# controllers.net
KiCad netlist of a schematic drawn in Altium Designer
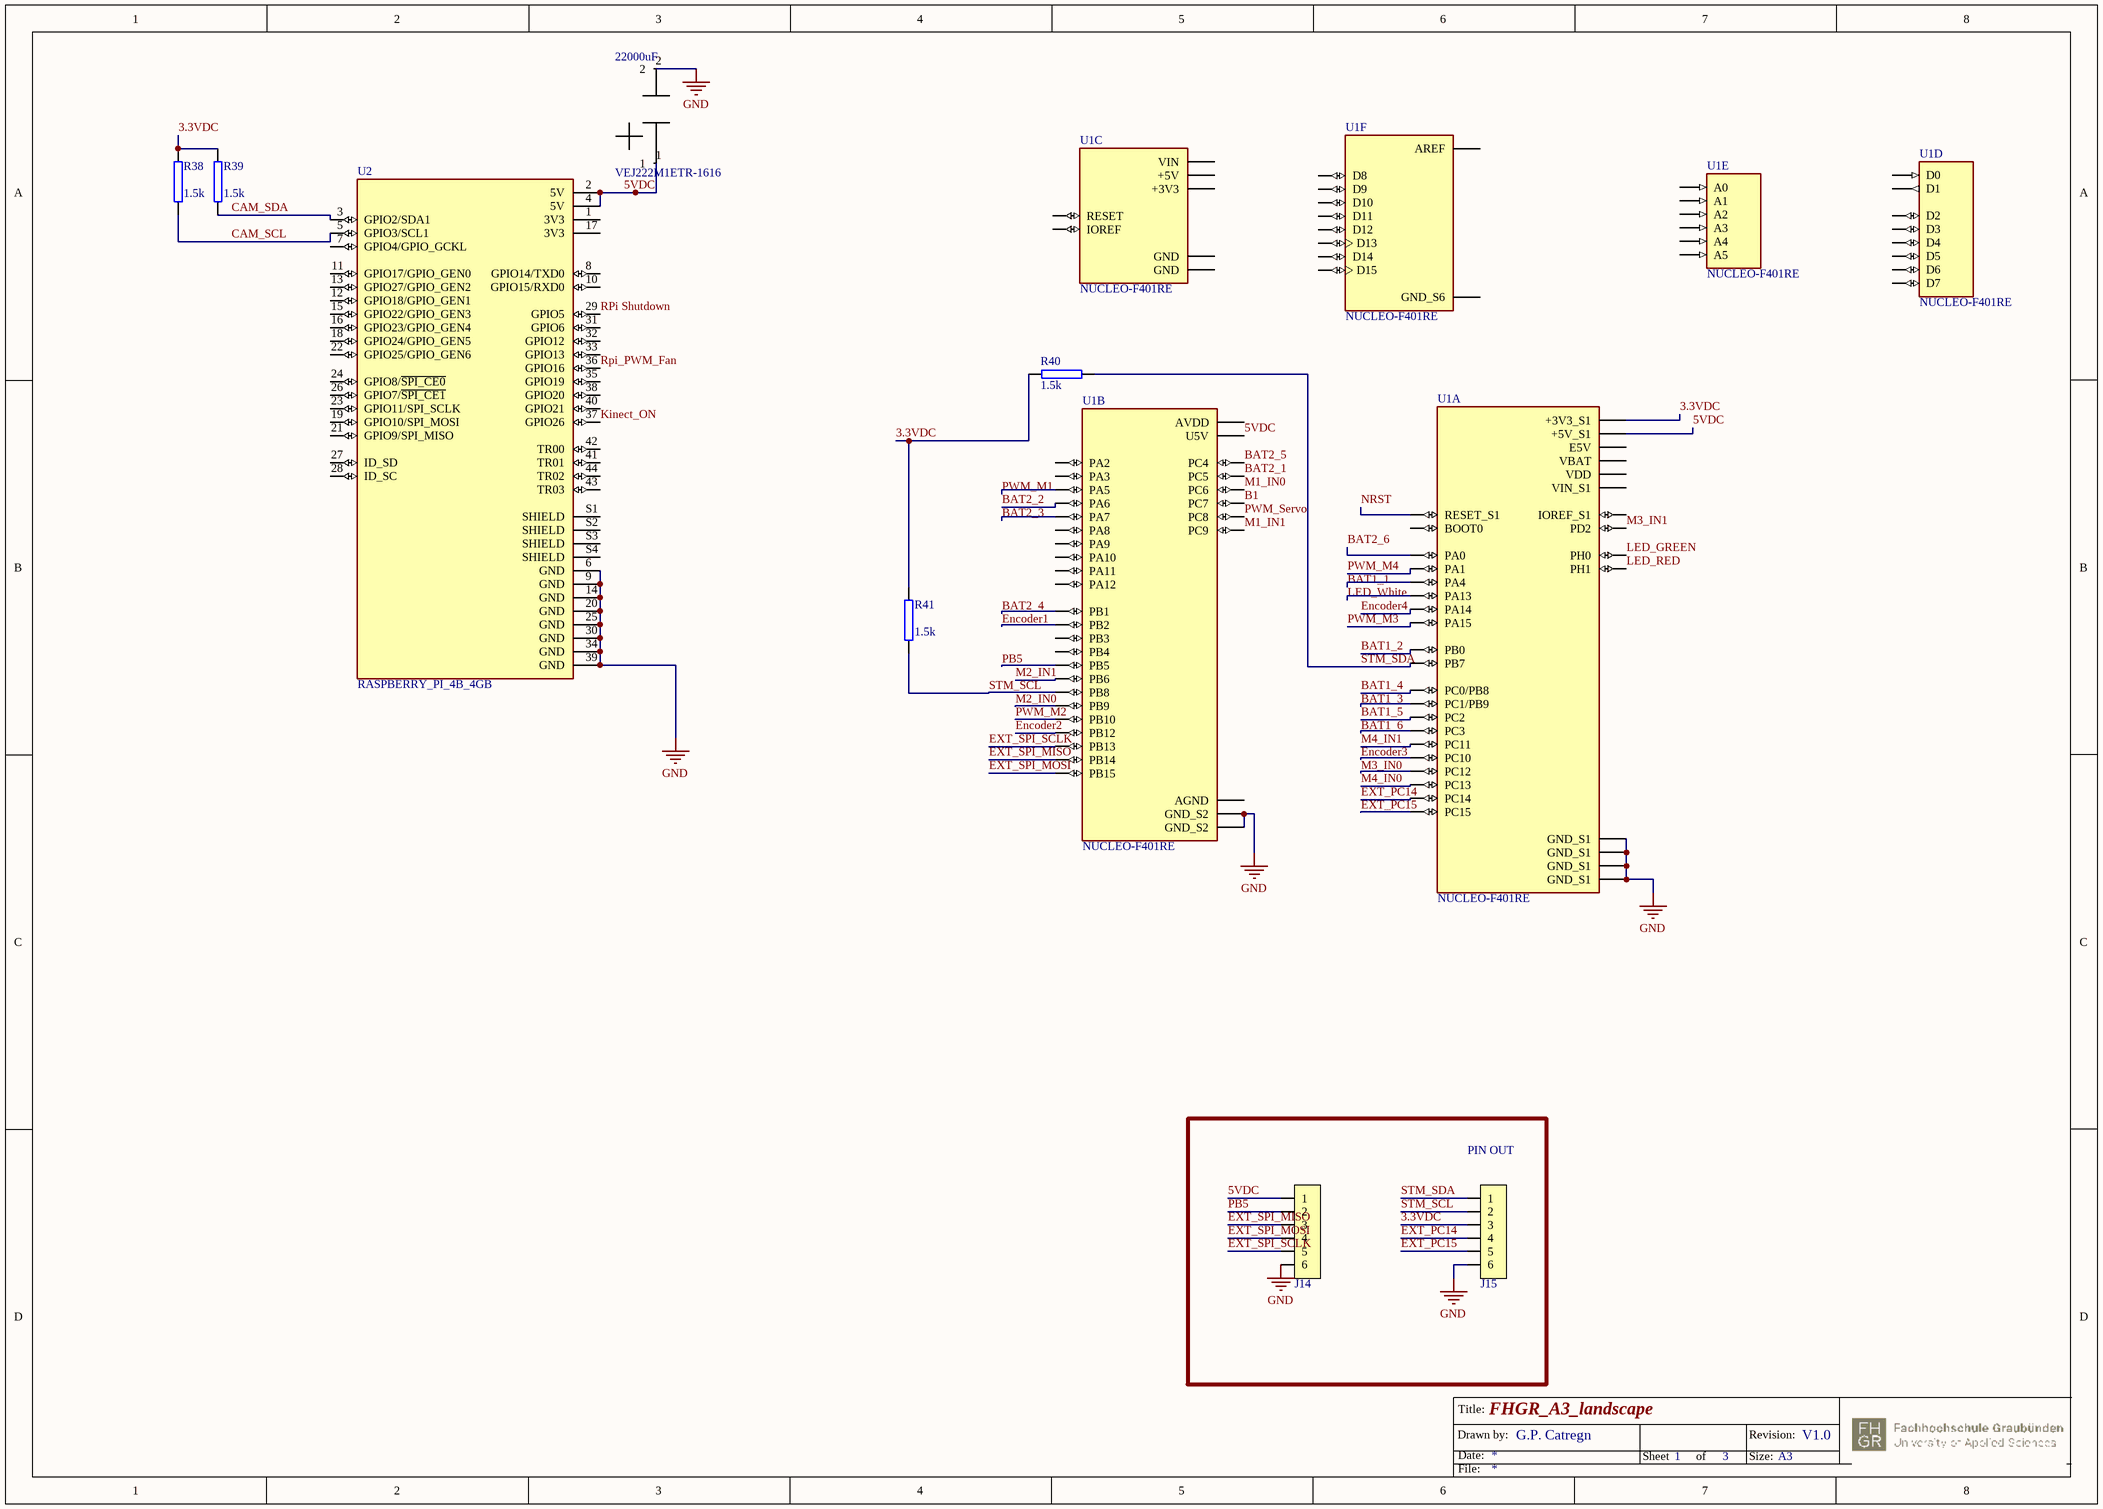
[diagram p0: controllers.SchDoc]

(export (version "E")
  (design (tool "Eeschema 10.0.6"))
  (components
    (comp (ref "22000uF")
      (value "VEJ222M1ETR-1616")
      (footprint "CAPAE180170X170M")
      (libsource (lib "VEJ222M1ETR-1616") (part "VEJ222M1ETR-1616"))
    )
    (comp (ref "J14")
      (value "6Pin_Male")
      (footprint "Header1x6_254")
      (libsource (lib "FHGR_Altium_database") (part "Connector6Pin"))
    )
    (comp (ref "J15")
      (value "6Pin_Male")
      (footprint "Header1x6_254")
      (libsource (lib "FHGR_Altium_database") (part "Connector6Pin"))
    )
    (comp (ref "R38")
      (value "1.5k")
      (footprint "0805")
      (fields (field (name "TOLERANCE") "1%") (field (name "Comment") "R 1K5 0805"))
      (libsource (lib "FHGR_Altium_database") (part "Resistor"))
    )
    (comp (ref "R39")
      (value "1.5k")
      (footprint "0805")
      (fields (field (name "TOLERANCE") "1%") (field (name "Comment") "R 1K5 0805"))
      (libsource (lib "FHGR_Altium_database") (part "Resistor"))
    )
    (comp (ref "R40")
      (value "1.5k")
      (footprint "0805")
      (fields (field (name "TOLERANCE") "1%") (field (name "Comment") "R 1K5 0805"))
      (libsource (lib "FHGR_Altium_database") (part "Resistor"))
    )
    (comp (ref "R41")
      (value "1.5k")
      (footprint "0805")
      (fields (field (name "TOLERANCE") "1%") (field (name "Comment") "R 1K5 0805"))
      (libsource (lib "FHGR_Altium_database") (part "Resistor"))
    )
    (comp (ref "U1")
      (value "NUCLEO-F401RE")
      (footprint "ST_NUCLEO-F401RE")
      (libsource (lib "NUCLEO-F401RE") (part "NUCLEO-F401RE"))
    )
    (comp (ref "U2")
      (value "RASPBERRY_PI_4B_4GB")
      (footprint "MODULE_RASPBERRY_PI_4B_4GB")
      (description "BCM2711 Raspberry Pi 4 Model B 4GB - ARMÂ® CortexÂ®-A72 MPU Embedded Evaluation Board")
      (fields (field (name "MF") "Raspberry Pi") (field (name "MP") "RASPBERRY PI 4B/4GB"))
      (libsource (lib "FH Graubünden") (part "RASPBERRY_PI_4B_4GB"))
    )
  )
  (nets
    (net (code "1") (name "/3.3VDC") (class "Default")
      (node (ref "J15") (pin "3") (pinfunction "3_3") (pintype "passive"))
      (node (ref "R38") (pin "2") (pintype "passive"))
      (node (ref "R39") (pin "2") (pintype "passive"))
      (node (ref "R40") (pin "2") (pintype "passive"))
      (node (ref "R41") (pin "2") (pintype "passive"))
      (node (ref "U1") (pin "CN7_16") (pinfunction "+3V3_S1_CN7_16") (pintype "power_in"))
    )
    (net (code "2") (name "/5VDC") (class "Default")
      (node (ref "22000uF") (pin "1") (pinfunction "1_1") (pintype "passive"))
      (node (ref "J14") (pin "1") (pinfunction "1_1") (pintype "passive"))
      (node (ref "U1") (pin "CN10_8") (pinfunction "U5V_CN10_8") (pintype "power_in"))
      (node (ref "U1") (pin "CN7_18") (pinfunction "+5V_S1_CN7_18") (pintype "power_in"))
      (node (ref "U2") (pin "2") (pinfunction "5V_2") (pintype "power_in"))
      (node (ref "U2") (pin "4") (pinfunction "5V_4") (pintype "power_in"))
    )
    (net (code "3") (name "/B1") (class "Default")
      (node (ref "U1") (pin "CN10_19") (pinfunction "PC7_CN10_19") (pintype "bidirectional"))
    )
    (net (code "4") (name "/BAT1_1") (class "Default")
      (node (ref "U1") (pin "CN7_32") (pinfunction "PA4_CN7_32") (pintype "bidirectional"))
    )
    (net (code "5") (name "/BAT1_2") (class "Default")
      (node (ref "U1") (pin "CN7_34") (pinfunction "PB0_CN7_34") (pintype "bidirectional"))
    )
    (net (code "6") (name "/BAT1_3") (class "Default")
      (node (ref "U1") (pin "CN7_36") (pinfunction "PC1/PB9_CN7_36") (pintype "bidirectional"))
    )
    (net (code "7") (name "/BAT1_4") (class "Default")
      (node (ref "U1") (pin "CN7_38") (pinfunction "PC0/PB8_CN7_38") (pintype "bidirectional"))
    )
    (net (code "8") (name "/BAT1_5") (class "Default")
      (node (ref "U1") (pin "CN7_35") (pinfunction "PC2_CN7_35") (pintype "bidirectional"))
    )
    (net (code "9") (name "/BAT1_6") (class "Default")
      (node (ref "U1") (pin "CN7_37") (pinfunction "PC3_CN7_37") (pintype "bidirectional"))
    )
    (net (code "10") (name "/BAT2_1") (class "Default")
      (node (ref "U1") (pin "CN10_6") (pinfunction "PC5_CN10_6") (pintype "bidirectional"))
    )
    (net (code "11") (name "/BAT2_2") (class "Default")
      (node (ref "U1") (pin "CN10_13") (pinfunction "PA6_CN10_13") (pintype "bidirectional"))
    )
    (net (code "12") (name "/BAT2_3") (class "Default")
      (node (ref "U1") (pin "CN10_15") (pinfunction "PA7_CN10_15") (pintype "bidirectional"))
    )
    (net (code "13") (name "/BAT2_4") (class "Default")
      (node (ref "U1") (pin "CN10_24") (pinfunction "PB1_CN10_24") (pintype "bidirectional"))
    )
    (net (code "14") (name "/BAT2_5") (class "Default")
      (node (ref "U1") (pin "CN10_34") (pinfunction "PC4_CN10_34") (pintype "bidirectional"))
    )
    (net (code "15") (name "/BAT2_6") (class "Default")
      (node (ref "U1") (pin "CN7_28") (pinfunction "PA0_CN7_28") (pintype "bidirectional"))
    )
    (net (code "16") (name "/CAM_SCL") (class "Default")
      (node (ref "R38") (pin "1") (pintype "passive"))
      (node (ref "U2") (pin "5") (pinfunction "GPIO3/SCL1_5") (pintype "bidirectional"))
    )
    (net (code "17") (name "/CAM_SDA") (class "Default")
      (node (ref "R39") (pin "1") (pintype "passive"))
      (node (ref "U2") (pin "3") (pinfunction "GPIO2/SDA1_3") (pintype "bidirectional"))
    )
    (net (code "18") (name "/EXT_PC14") (class "Default")
      (node (ref "J15") (pin "4") (pinfunction "4_4") (pintype "passive"))
      (node (ref "U1") (pin "CN7_25") (pinfunction "PC14_CN7_25") (pintype "bidirectional"))
    )
    (net (code "19") (name "/EXT_PC15") (class "Default")
      (node (ref "J15") (pin "5") (pinfunction "5_5") (pintype "passive"))
      (node (ref "U1") (pin "CN7_27") (pinfunction "PC15_CN7_27") (pintype "bidirectional"))
    )
    (net (code "20") (name "/EXT_SPI_MISO") (class "Default")
      (node (ref "J14") (pin "3") (pinfunction "3_3") (pintype "passive"))
      (node (ref "U1") (pin "CN10_28") (pinfunction "PB14_CN10_28") (pintype "bidirectional"))
    )
    (net (code "21") (name "/EXT_SPI_MOSI") (class "Default")
      (node (ref "J14") (pin "4") (pinfunction "4_4") (pintype "passive"))
      (node (ref "U1") (pin "CN10_26") (pinfunction "PB15_CN10_26") (pintype "bidirectional"))
    )
    (net (code "22") (name "/EXT_SPI_SCLK") (class "Default")
      (node (ref "J14") (pin "5") (pinfunction "5_5") (pintype "passive"))
      (node (ref "U1") (pin "CN10_30") (pinfunction "PB13_CN10_30") (pintype "bidirectional"))
    )
    (net (code "23") (name "/Encoder1") (class "Default")
      (node (ref "U1") (pin "CN10_22") (pinfunction "PB2_CN10_22") (pintype "bidirectional"))
    )
    (net (code "24") (name "/Encoder2") (class "Default")
      (node (ref "U1") (pin "CN10_16") (pinfunction "PB12_CN10_16") (pintype "bidirectional"))
    )
    (net (code "25") (name "/Encoder3") (class "Default")
      (node (ref "U1") (pin "CN7_1") (pinfunction "PC10_CN7_1") (pintype "bidirectional"))
    )
    (net (code "26") (name "/Encoder4") (class "Default")
      (node (ref "U1") (pin "CN7_15") (pinfunction "PA14_CN7_15") (pintype "bidirectional"))
    )
    (net (code "27") (name "/Kinect_ON") (class "Default")
      (node (ref "U2") (pin "37") (pinfunction "GPIO26_37") (pintype "bidirectional"))
    )
    (net (code "28") (name "/LED_GREEN") (class "Default")
      (node (ref "U1") (pin "CN7_29") (pinfunction "PH0_CN7_29") (pintype "bidirectional"))
    )
    (net (code "29") (name "/LED_RED") (class "Default")
      (node (ref "U1") (pin "CN7_31") (pinfunction "PH1_CN7_31") (pintype "bidirectional"))
    )
    (net (code "30") (name "/LED_White") (class "Default")
      (node (ref "U1") (pin "CN7_13") (pinfunction "PA13_CN7_13") (pintype "bidirectional"))
    )
    (net (code "31") (name "/M1_IN0") (class "Default")
      (node (ref "U1") (pin "CN10_4") (pinfunction "PC6_CN10_4") (pintype "bidirectional"))
    )
    (net (code "32") (name "/M1_IN1") (class "Default")
      (node (ref "U1") (pin "CN10_1") (pinfunction "PC9_CN10_1") (pintype "bidirectional"))
    )
    (net (code "33") (name "/M2_IN0") (class "Default")
      (node (ref "U1") (pin "CN10_5") (pinfunction "PB9_CN10_5") (pintype "bidirectional"))
    )
    (net (code "34") (name "/M2_IN1") (class "Default")
      (node (ref "U1") (pin "CN10_17") (pinfunction "PB6_CN10_17") (pintype "bidirectional"))
    )
    (net (code "35") (name "/M3_IN0") (class "Default")
      (node (ref "U1") (pin "CN7_3") (pinfunction "PC12_CN7_3") (pintype "bidirectional"))
    )
    (net (code "36") (name "/M3_IN1") (class "Default")
      (node (ref "U1") (pin "CN7_4") (pinfunction "PD2_CN7_4") (pintype "bidirectional"))
    )
    (net (code "37") (name "/M4_IN0") (class "Default")
      (node (ref "U1") (pin "CN7_23") (pinfunction "PC13_CN7_23") (pintype "bidirectional"))
    )
    (net (code "38") (name "/M4_IN1") (class "Default")
      (node (ref "U1") (pin "CN7_2") (pinfunction "PC11_CN7_2") (pintype "bidirectional"))
    )
    (net (code "39") (name "/NRST") (class "Default")
      (node (ref "U1") (pin "CN7_14") (pinfunction "RESET_S1_CN7_14") (pintype "bidirectional"))
    )
    (net (code "40") (name "/PB5") (class "Default")
      (node (ref "J14") (pin "2") (pinfunction "2_2") (pintype "passive"))
      (node (ref "U1") (pin "CN10_29") (pinfunction "PB5_CN10_29") (pintype "bidirectional"))
    )
    (net (code "41") (name "/PWM_M1") (class "Default")
      (node (ref "U1") (pin "CN10_11") (pinfunction "PA5_CN10_11") (pintype "bidirectional"))
    )
    (net (code "42") (name "/PWM_M2") (class "Default")
      (node (ref "U1") (pin "CN10_25") (pinfunction "PB10_CN10_25") (pintype "bidirectional"))
    )
    (net (code "43") (name "/PWM_M3") (class "Default")
      (node (ref "U1") (pin "CN7_17") (pinfunction "PA15_CN7_17") (pintype "bidirectional"))
    )
    (net (code "44") (name "/PWM_M4") (class "Default")
      (node (ref "U1") (pin "CN7_30") (pinfunction "PA1_CN7_30") (pintype "bidirectional"))
    )
    (net (code "45") (name "/PWM_Servo") (class "Default")
      (node (ref "U1") (pin "CN10_2") (pinfunction "PC8_CN10_2") (pintype "bidirectional"))
    )
    (net (code "46") (name "/RPi Shutdown") (class "Default")
      (node (ref "U2") (pin "29") (pinfunction "GPIO5_29") (pintype "bidirectional"))
    )
    (net (code "47") (name "/Rpi_PWM_Fan") (class "Default")
      (node (ref "U2") (pin "36") (pinfunction "GPIO16_36") (pintype "bidirectional"))
    )
    (net (code "48") (name "/STM_SCL") (class "Default")
      (node (ref "J15") (pin "2") (pinfunction "2_2") (pintype "passive"))
      (node (ref "R41") (pin "1") (pintype "passive"))
      (node (ref "U1") (pin "CN10_3") (pinfunction "PB8_CN10_3") (pintype "bidirectional"))
    )
    (net (code "49") (name "/STM_SDA") (class "Default")
      (node (ref "J15") (pin "1") (pinfunction "1_1") (pintype "passive"))
      (node (ref "R40") (pin "1") (pintype "passive"))
      (node (ref "U1") (pin "CN7_21") (pinfunction "PB7_CN7_21") (pintype "bidirectional"))
    )
    (net (code "50") (name "GND") (class "Default")
      (node (ref "22000uF") (pin "2") (pinfunction "2_2") (pintype "passive"))
      (node (ref "J14") (pin "6") (pinfunction "6_6") (pintype "passive"))
      (node (ref "J15") (pin "6") (pinfunction "6_6") (pintype "passive"))
      (node (ref "U1") (pin "CN10_20") (pinfunction "GND_S2_CN10_20") (pintype "power_in"))
      (node (ref "U1") (pin "CN10_9") (pinfunction "GND_S2_CN10_9") (pintype "power_in"))
      (node (ref "U1") (pin "CN7_19") (pinfunction "GND_S1_CN7_19") (pintype "power_in"))
      (node (ref "U1") (pin "CN7_20") (pinfunction "GND_S1_CN7_20") (pintype "power_in"))
      (node (ref "U1") (pin "CN7_22") (pinfunction "GND_S1_CN7_22") (pintype "power_in"))
      (node (ref "U1") (pin "CN7_8") (pinfunction "GND_S1_CN7_8") (pintype "power_in"))
      (node (ref "U2") (pin "14") (pinfunction "GND_14") (pintype "power_in"))
      (node (ref "U2") (pin "20") (pinfunction "GND_20") (pintype "power_in"))
      (node (ref "U2") (pin "25") (pinfunction "GND_25") (pintype "power_in"))
      (node (ref "U2") (pin "30") (pinfunction "GND_30") (pintype "power_in"))
      (node (ref "U2") (pin "34") (pinfunction "GND_34") (pintype "power_in"))
      (node (ref "U2") (pin "39") (pinfunction "GND_39") (pintype "power_in"))
      (node (ref "U2") (pin "6") (pinfunction "GND_6") (pintype "power_in"))
      (node (ref "U2") (pin "9") (pinfunction "GND_9") (pintype "power_in"))
    )
    (net (code "51") (name "unconnected-(U1A-BOOT0-PadCN7_7)") (class "Default")
      (node (ref "U1") (pin "CN7_7") (pinfunction "BOOT0_CN7_7") (pintype "bidirectional"))
    )
    (net (code "52") (name "unconnected-(U1A-E5V-PadCN7_6)") (class "Default")
      (node (ref "U1") (pin "CN7_6") (pinfunction "E5V_CN7_6") (pintype "power_in"))
    )
    (net (code "53") (name "unconnected-(U1A-IOREF_S1-PadCN7_12)") (class "Default")
      (node (ref "U1") (pin "CN7_12") (pinfunction "IOREF_S1_CN7_12") (pintype "bidirectional"))
    )
    (net (code "54") (name "unconnected-(U1A-VBAT-PadCN7_33)") (class "Default")
      (node (ref "U1") (pin "CN7_33") (pinfunction "VBAT_CN7_33") (pintype "power_in"))
    )
    (net (code "55") (name "unconnected-(U1A-VDD-PadCN7_5)") (class "Default")
      (node (ref "U1") (pin "CN7_5") (pinfunction "VDD_CN7_5") (pintype "power_in"))
    )
    (net (code "56") (name "unconnected-(U1A-VIN_S1-PadCN7_24)") (class "Default")
      (node (ref "U1") (pin "CN7_24") (pinfunction "VIN_S1_CN7_24") (pintype "power_in"))
    )
    (net (code "57") (name "unconnected-(U1B-AGND-PadCN10_32)") (class "Default")
      (node (ref "U1") (pin "CN10_32") (pinfunction "AGND_CN10_32") (pintype "power_in"))
    )
    (net (code "58") (name "unconnected-(U1B-AVDD-PadCN10_7)") (class "Default")
      (node (ref "U1") (pin "CN10_7") (pinfunction "AVDD_CN10_7") (pintype "power_in"))
    )
    (net (code "59") (name "unconnected-(U1B-PA2-PadCN10_35)") (class "Default")
      (node (ref "U1") (pin "CN10_35") (pinfunction "PA2_CN10_35") (pintype "bidirectional"))
    )
    (net (code "60") (name "unconnected-(U1B-PA3-PadCN10_37)") (class "Default")
      (node (ref "U1") (pin "CN10_37") (pinfunction "PA3_CN10_37") (pintype "bidirectional"))
    )
    (net (code "61") (name "unconnected-(U1B-PA8-PadCN10_23)") (class "Default")
      (node (ref "U1") (pin "CN10_23") (pinfunction "PA8_CN10_23") (pintype "bidirectional"))
    )
    (net (code "62") (name "unconnected-(U1B-PA9-PadCN10_21)") (class "Default")
      (node (ref "U1") (pin "CN10_21") (pinfunction "PA9_CN10_21") (pintype "bidirectional"))
    )
    (net (code "63") (name "unconnected-(U1B-PA10-PadCN10_33)") (class "Default")
      (node (ref "U1") (pin "CN10_33") (pinfunction "PA10_CN10_33") (pintype "bidirectional"))
    )
    (net (code "64") (name "unconnected-(U1B-PA11-PadCN10_14)") (class "Default")
      (node (ref "U1") (pin "CN10_14") (pinfunction "PA11_CN10_14") (pintype "bidirectional"))
    )
    (net (code "65") (name "unconnected-(U1B-PA12-PadCN10_12)") (class "Default")
      (node (ref "U1") (pin "CN10_12") (pinfunction "PA12_CN10_12") (pintype "bidirectional"))
    )
    (net (code "66") (name "unconnected-(U1B-PB3-PadCN10_31)") (class "Default")
      (node (ref "U1") (pin "CN10_31") (pinfunction "PB3_CN10_31") (pintype "bidirectional"))
    )
    (net (code "67") (name "unconnected-(U1B-PB4-PadCN10_27)") (class "Default")
      (node (ref "U1") (pin "CN10_27") (pinfunction "PB4_CN10_27") (pintype "bidirectional"))
    )
    (net (code "68") (name "unconnected-(U1C-+3V3-PadCN6_4)") (class "Default")
      (node (ref "U1") (pin "CN6_4") (pinfunction "+3V3_CN6_4") (pintype "power_in"))
    )
    (net (code "69") (name "unconnected-(U1C-+5V-PadCN6_5)") (class "Default")
      (node (ref "U1") (pin "CN6_5") (pinfunction "+5V_CN6_5") (pintype "power_in"))
    )
    (net (code "70") (name "unconnected-(U1C-GND-PadCN6_6)") (class "Default")
      (node (ref "U1") (pin "CN6_6") (pinfunction "GND_CN6_6") (pintype "power_in"))
    )
    (net (code "71") (name "unconnected-(U1C-GND-PadCN6_7)") (class "Default")
      (node (ref "U1") (pin "CN6_7") (pinfunction "GND_CN6_7") (pintype "power_in"))
    )
    (net (code "72") (name "unconnected-(U1C-IOREF-PadCN6_2)") (class "Default")
      (node (ref "U1") (pin "CN6_2") (pinfunction "IOREF_CN6_2") (pintype "bidirectional"))
    )
    (net (code "73") (name "unconnected-(U1C-RESET-PadCN6_3)") (class "Default")
      (node (ref "U1") (pin "CN6_3") (pinfunction "RESET_CN6_3") (pintype "bidirectional"))
    )
    (net (code "74") (name "unconnected-(U1C-VIN-PadCN6_8)") (class "Default")
      (node (ref "U1") (pin "CN6_8") (pinfunction "VIN_CN6_8") (pintype "power_in"))
    )
    (net (code "75") (name "unconnected-(U1D-D0-PadCN9_1)") (class "Default")
      (node (ref "U1") (pin "CN9_1") (pinfunction "D0_CN9_1") (pintype "input"))
    )
    (net (code "76") (name "unconnected-(U1D-D1-PadCN9_2)") (class "Default")
      (node (ref "U1") (pin "CN9_2") (pinfunction "D1_CN9_2") (pintype "output"))
    )
    (net (code "77") (name "unconnected-(U1D-D2-PadCN9_3)") (class "Default")
      (node (ref "U1") (pin "CN9_3") (pinfunction "D2_CN9_3") (pintype "bidirectional"))
    )
    (net (code "78") (name "unconnected-(U1D-D3-PadCN9_4)") (class "Default")
      (node (ref "U1") (pin "CN9_4") (pinfunction "D3_CN9_4") (pintype "bidirectional"))
    )
    (net (code "79") (name "unconnected-(U1D-D4-PadCN9_5)") (class "Default")
      (node (ref "U1") (pin "CN9_5") (pinfunction "D4_CN9_5") (pintype "bidirectional"))
    )
    (net (code "80") (name "unconnected-(U1D-D5-PadCN9_6)") (class "Default")
      (node (ref "U1") (pin "CN9_6") (pinfunction "D5_CN9_6") (pintype "bidirectional"))
    )
    (net (code "81") (name "unconnected-(U1D-D6-PadCN9_7)") (class "Default")
      (node (ref "U1") (pin "CN9_7") (pinfunction "D6_CN9_7") (pintype "bidirectional"))
    )
    (net (code "82") (name "unconnected-(U1D-D7-PadCN9_8)") (class "Default")
      (node (ref "U1") (pin "CN9_8") (pinfunction "D7_CN9_8") (pintype "bidirectional"))
    )
    (net (code "83") (name "unconnected-(U1E-A0-PadCN8_1)") (class "Default")
      (node (ref "U1") (pin "CN8_1") (pinfunction "A0_CN8_1") (pintype "input"))
    )
    (net (code "84") (name "unconnected-(U1E-A1-PadCN8_2)") (class "Default")
      (node (ref "U1") (pin "CN8_2") (pinfunction "A1_CN8_2") (pintype "input"))
    )
    (net (code "85") (name "unconnected-(U1E-A2-PadCN8_3)") (class "Default")
      (node (ref "U1") (pin "CN8_3") (pinfunction "A2_CN8_3") (pintype "input"))
    )
    (net (code "86") (name "unconnected-(U1E-A3-PadCN8_4)") (class "Default")
      (node (ref "U1") (pin "CN8_4") (pinfunction "A3_CN8_4") (pintype "input"))
    )
    (net (code "87") (name "unconnected-(U1E-A4-PadCN8_5)") (class "Default")
      (node (ref "U1") (pin "CN8_5") (pinfunction "A4_CN8_5") (pintype "input"))
    )
    (net (code "88") (name "unconnected-(U1E-A5-PadCN8_6)") (class "Default")
      (node (ref "U1") (pin "CN8_6") (pinfunction "A5_CN8_6") (pintype "input"))
    )
    (net (code "89") (name "unconnected-(U1F-AREF-PadCN5_8)") (class "Default")
      (node (ref "U1") (pin "CN5_8") (pinfunction "AREF_CN5_8") (pintype "power_in"))
    )
    (net (code "90") (name "unconnected-(U1F-D8-PadCN5_1)") (class "Default")
      (node (ref "U1") (pin "CN5_1") (pinfunction "D8_CN5_1") (pintype "bidirectional"))
    )
    (net (code "91") (name "unconnected-(U1F-D9-PadCN5_2)") (class "Default")
      (node (ref "U1") (pin "CN5_2") (pinfunction "D9_CN5_2") (pintype "bidirectional"))
    )
    (net (code "92") (name "unconnected-(U1F-D10-PadCN5_3)") (class "Default")
      (node (ref "U1") (pin "CN5_3") (pinfunction "D10_CN5_3") (pintype "bidirectional"))
    )
    (net (code "93") (name "unconnected-(U1F-D11-PadCN5_4)") (class "Default")
      (node (ref "U1") (pin "CN5_4") (pinfunction "D11_CN5_4") (pintype "bidirectional"))
    )
    (net (code "94") (name "unconnected-(U1F-D12-PadCN5_5)") (class "Default")
      (node (ref "U1") (pin "CN5_5") (pinfunction "D12_CN5_5") (pintype "bidirectional"))
    )
    (net (code "95") (name "unconnected-(U1F-D13-PadCN5_6)") (class "Default")
      (node (ref "U1") (pin "CN5_6") (pinfunction "D13_CN5_6") (pintype "bidirectional"))
    )
    (net (code "96") (name "unconnected-(U1F-D14-PadCN5_9)") (class "Default")
      (node (ref "U1") (pin "CN5_9") (pinfunction "D14_CN5_9") (pintype "bidirectional"))
    )
    (net (code "97") (name "unconnected-(U1F-D15-PadCN5_10)") (class "Default")
      (node (ref "U1") (pin "CN5_10") (pinfunction "D15_CN5_10") (pintype "bidirectional"))
    )
    (net (code "98") (name "unconnected-(U1F-GND_S6-PadCN5_7)") (class "Default")
      (node (ref "U1") (pin "CN5_7") (pinfunction "GND_S6_CN5_7") (pintype "power_in"))
    )
    (net (code "99") (name "unconnected-(U2-3V3-Pad1)") (class "Default")
      (node (ref "U2") (pin "1") (pinfunction "3V3_1") (pintype "power_in"))
    )
    (net (code "100") (name "unconnected-(U2-3V3-Pad17)") (class "Default")
      (node (ref "U2") (pin "17") (pinfunction "3V3_17") (pintype "power_in"))
    )
    (net (code "101") (name "unconnected-(U2-GPIO4{slash}GPIO_GCKL-Pad7)") (class "Default")
      (node (ref "U2") (pin "7") (pinfunction "GPIO4/GPIO_GCKL_7") (pintype "bidirectional"))
    )
    (net (code "102") (name "unconnected-(U2-GPIO6-Pad31)") (class "Default")
      (node (ref "U2") (pin "31") (pinfunction "GPIO6_31") (pintype "bidirectional"))
    )
    (net (code "103") (name "unconnected-(U2-GPIO7{slash}~{SPI_CE1}-Pad26)") (class "Default")
      (node (ref "U2") (pin "26") (pinfunction "GPIO7/~{SPI_CE1}_26") (pintype "bidirectional"))
    )
    (net (code "104") (name "unconnected-(U2-GPIO8{slash}~{SPI_CE0}-Pad24)") (class "Default")
      (node (ref "U2") (pin "24") (pinfunction "GPIO8/~{SPI_CE0}_24") (pintype "bidirectional"))
    )
    (net (code "105") (name "unconnected-(U2-GPIO9{slash}SPI_MISO-Pad21)") (class "Default")
      (node (ref "U2") (pin "21") (pinfunction "GPIO9/SPI_MISO_21") (pintype "bidirectional"))
    )
    (net (code "106") (name "unconnected-(U2-GPIO10{slash}SPI_MOSI-Pad19)") (class "Default")
      (node (ref "U2") (pin "19") (pinfunction "GPIO10/SPI_MOSI_19") (pintype "bidirectional"))
    )
    (net (code "107") (name "unconnected-(U2-GPIO11{slash}SPI_SCLK-Pad23)") (class "Default")
      (node (ref "U2") (pin "23") (pinfunction "GPIO11/SPI_SCLK_23") (pintype "bidirectional"))
    )
    (net (code "108") (name "unconnected-(U2-GPIO12-Pad32)") (class "Default")
      (node (ref "U2") (pin "32") (pinfunction "GPIO12_32") (pintype "bidirectional"))
    )
    (net (code "109") (name "unconnected-(U2-GPIO13-Pad33)") (class "Default")
      (node (ref "U2") (pin "33") (pinfunction "GPIO13_33") (pintype "bidirectional"))
    )
    (net (code "110") (name "unconnected-(U2-GPIO14{slash}TXD0-Pad8)") (class "Default")
      (node (ref "U2") (pin "8") (pinfunction "GPIO14/TXD0_8") (pintype "bidirectional"))
    )
    (net (code "111") (name "unconnected-(U2-GPIO15{slash}RXD0-Pad10)") (class "Default")
      (node (ref "U2") (pin "10") (pinfunction "GPIO15/RXD0_10") (pintype "bidirectional"))
    )
    (net (code "112") (name "unconnected-(U2-GPIO17{slash}GPIO_GEN0-Pad11)") (class "Default")
      (node (ref "U2") (pin "11") (pinfunction "GPIO17/GPIO_GEN0_11") (pintype "bidirectional"))
    )
    (net (code "113") (name "unconnected-(U2-GPIO18{slash}GPIO_GEN1-Pad12)") (class "Default")
      (node (ref "U2") (pin "12") (pinfunction "GPIO18/GPIO_GEN1_12") (pintype "bidirectional"))
    )
    (net (code "114") (name "unconnected-(U2-GPIO19-Pad35)") (class "Default")
      (node (ref "U2") (pin "35") (pinfunction "GPIO19_35") (pintype "bidirectional"))
    )
    (net (code "115") (name "unconnected-(U2-GPIO20-Pad38)") (class "Default")
      (node (ref "U2") (pin "38") (pinfunction "GPIO20_38") (pintype "bidirectional"))
    )
    (net (code "116") (name "unconnected-(U2-GPIO21-Pad40)") (class "Default")
      (node (ref "U2") (pin "40") (pinfunction "GPIO21_40") (pintype "bidirectional"))
    )
    (net (code "117") (name "unconnected-(U2-GPIO22{slash}GPIO_GEN3-Pad15)") (class "Default")
      (node (ref "U2") (pin "15") (pinfunction "GPIO22/GPIO_GEN3_15") (pintype "bidirectional"))
    )
    (net (code "118") (name "unconnected-(U2-GPIO23{slash}GPIO_GEN4-Pad16)") (class "Default")
      (node (ref "U2") (pin "16") (pinfunction "GPIO23/GPIO_GEN4_16") (pintype "bidirectional"))
    )
    (net (code "119") (name "unconnected-(U2-GPIO24{slash}GPIO_GEN5-Pad18)") (class "Default")
      (node (ref "U2") (pin "18") (pinfunction "GPIO24/GPIO_GEN5_18") (pintype "bidirectional"))
    )
    (net (code "120") (name "unconnected-(U2-GPIO25{slash}GPIO_GEN6-Pad22)") (class "Default")
      (node (ref "U2") (pin "22") (pinfunction "GPIO25/GPIO_GEN6_22") (pintype "bidirectional"))
    )
    (net (code "121") (name "unconnected-(U2-GPIO27{slash}GPIO_GEN2-Pad13)") (class "Default")
      (node (ref "U2") (pin "13") (pinfunction "GPIO27/GPIO_GEN2_13") (pintype "bidirectional"))
    )
    (net (code "122") (name "unconnected-(U2-ID_SC-Pad28)") (class "Default")
      (node (ref "U2") (pin "28") (pinfunction "ID_SC_28") (pintype "bidirectional"))
    )
    (net (code "123") (name "unconnected-(U2-ID_SD-Pad27)") (class "Default")
      (node (ref "U2") (pin "27") (pinfunction "ID_SD_27") (pintype "bidirectional"))
    )
    (net (code "124") (name "unconnected-(U2-SHIELD-PadS1)") (class "Default")
      (node (ref "U2") (pin "S1") (pinfunction "SHIELD_S1") (pintype "power_in"))
    )
    (net (code "125") (name "unconnected-(U2-SHIELD-PadS2)") (class "Default")
      (node (ref "U2") (pin "S2") (pinfunction "SHIELD_S2") (pintype "power_in"))
    )
    (net (code "126") (name "unconnected-(U2-SHIELD-PadS3)") (class "Default")
      (node (ref "U2") (pin "S3") (pinfunction "SHIELD_S3") (pintype "power_in"))
    )
    (net (code "127") (name "unconnected-(U2-SHIELD-PadS4)") (class "Default")
      (node (ref "U2") (pin "S4") (pinfunction "SHIELD_S4") (pintype "power_in"))
    )
    (net (code "128") (name "unconnected-(U2-TR00-Pad42)") (class "Default")
      (node (ref "U2") (pin "42") (pinfunction "TR00_42") (pintype "bidirectional"))
    )
    (net (code "129") (name "unconnected-(U2-TR01-Pad41)") (class "Default")
      (node (ref "U2") (pin "41") (pinfunction "TR01_41") (pintype "bidirectional"))
    )
    (net (code "130") (name "unconnected-(U2-TR02-Pad44)") (class "Default")
      (node (ref "U2") (pin "44") (pinfunction "TR02_44") (pintype "bidirectional"))
    )
    (net (code "131") (name "unconnected-(U2-TR03-Pad43)") (class "Default")
      (node (ref "U2") (pin "43") (pinfunction "TR03_43") (pintype "bidirectional"))
    )
  )
)
